# SCH_CJ4_Audiopanel.net
KiCad netlist of a schematic drawn in EasyEDA
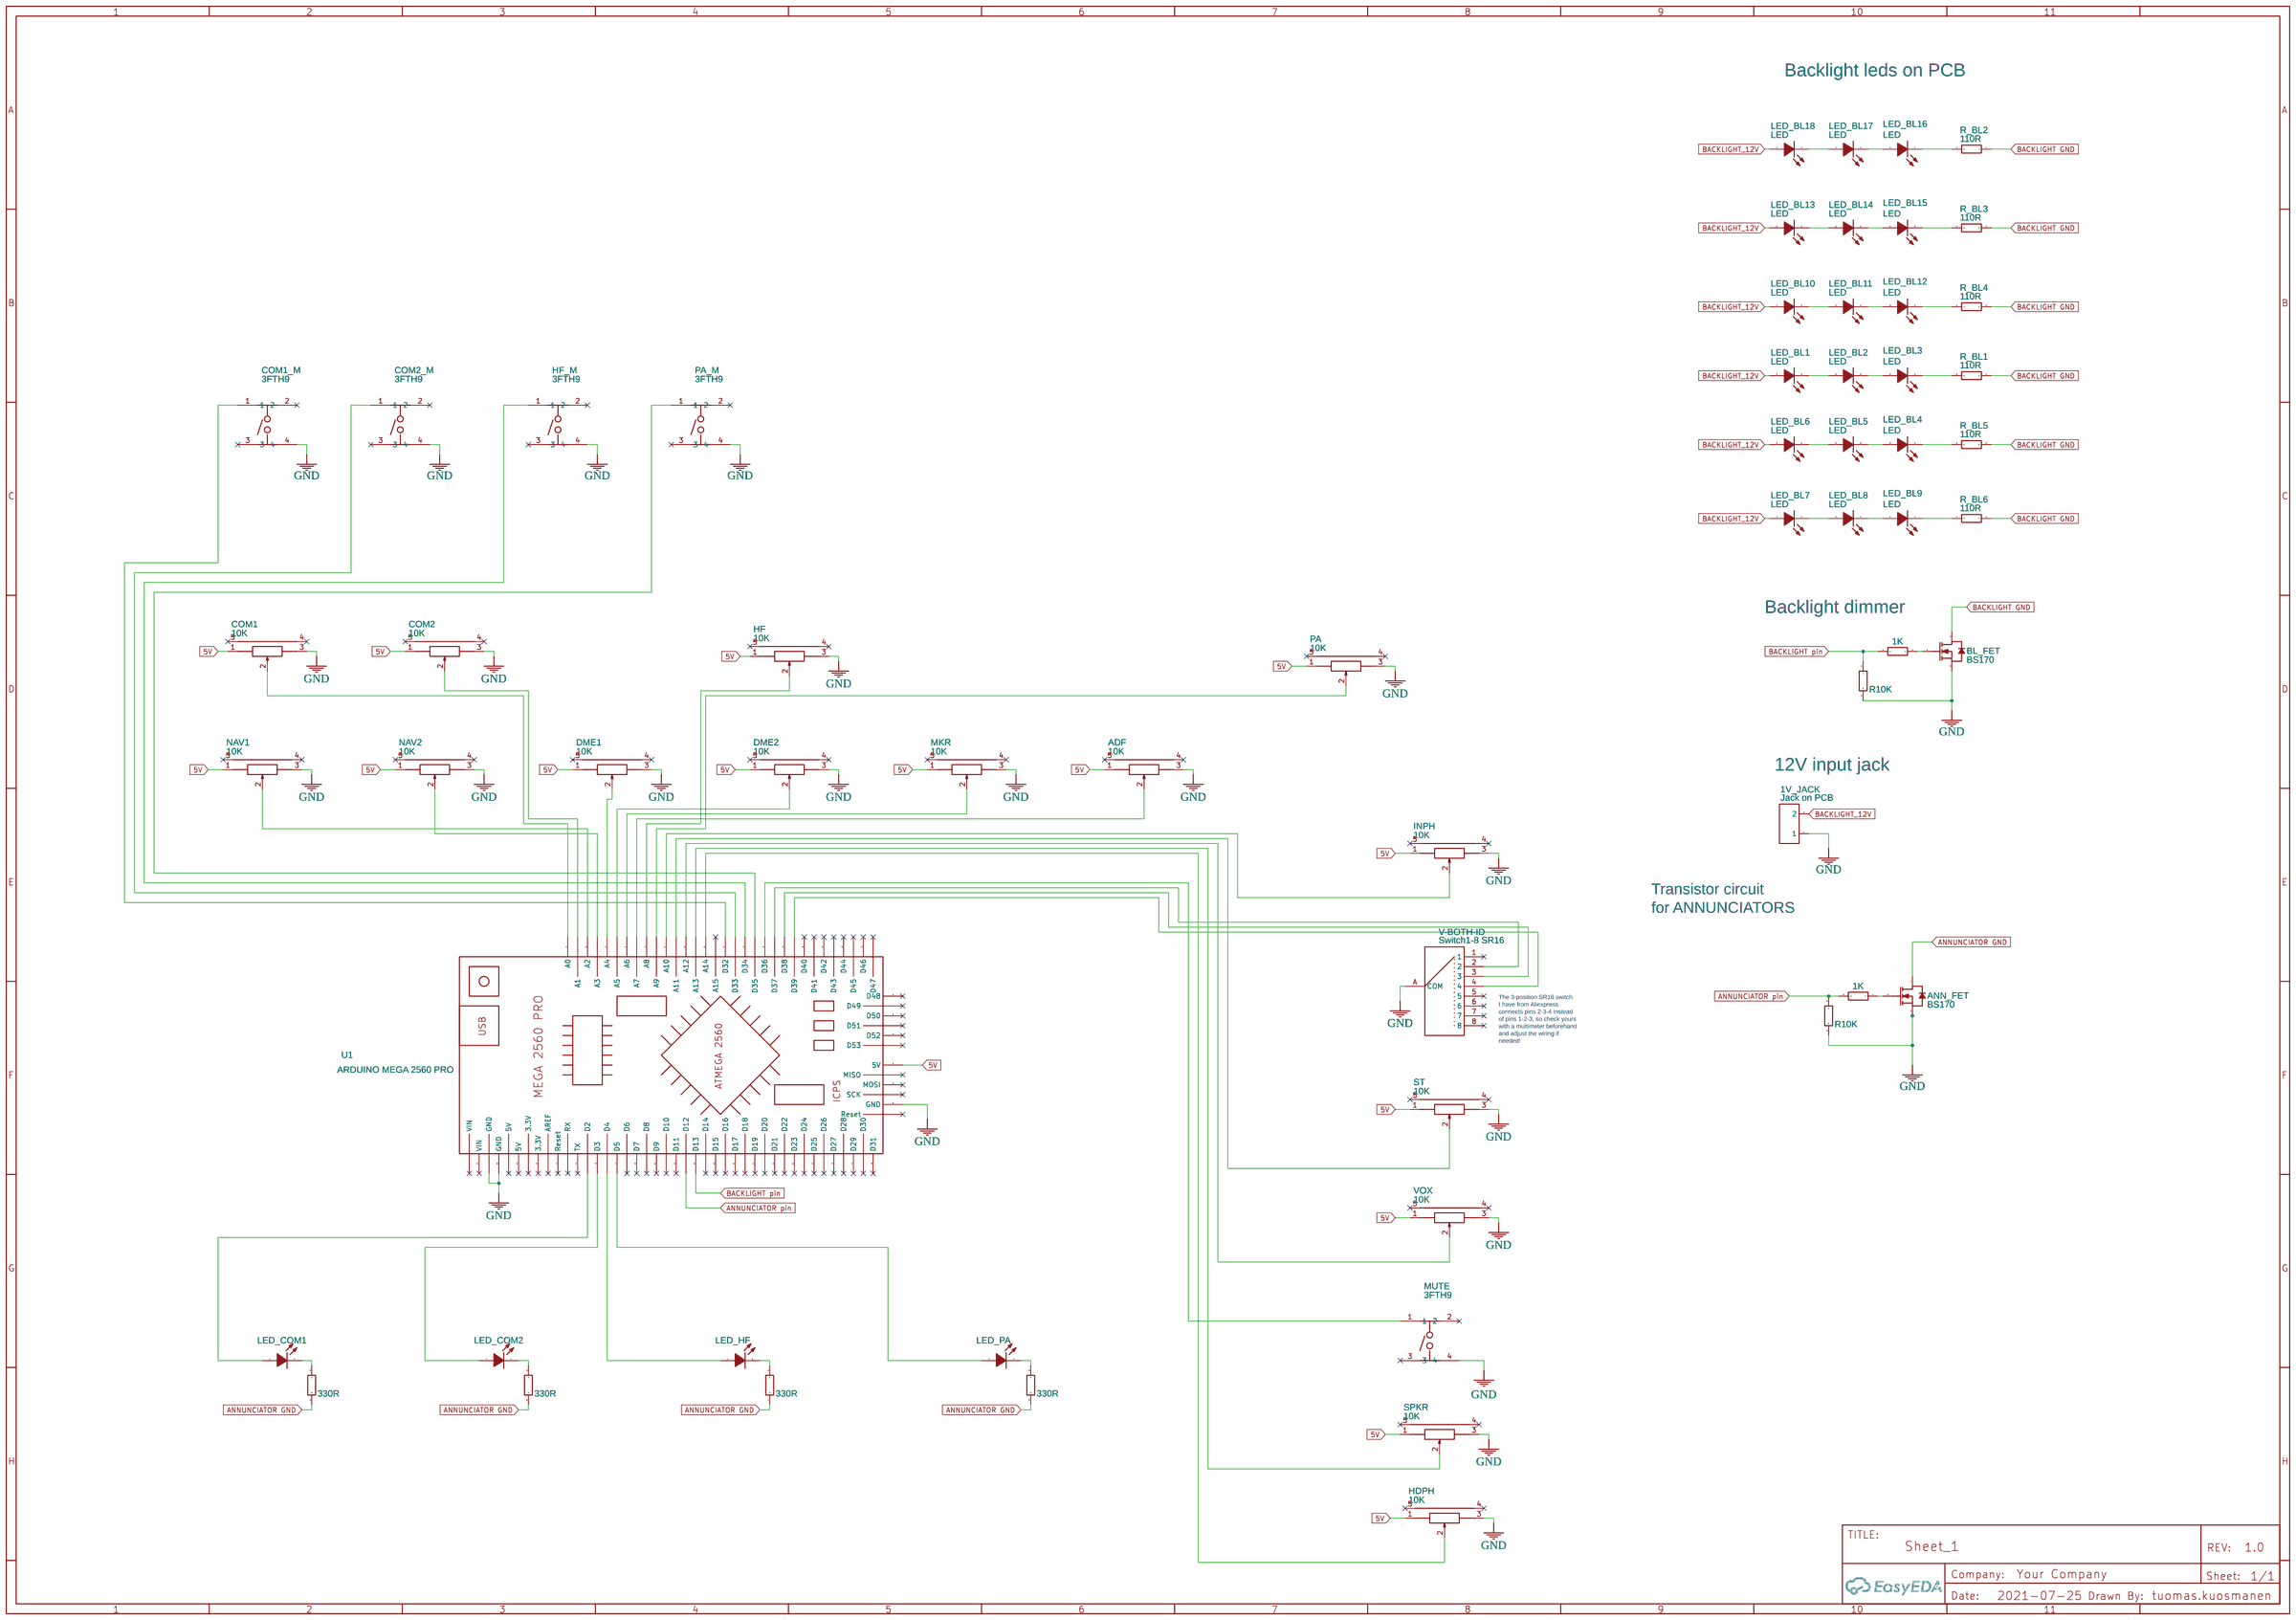
[diagram p0: schematic sheet]

(export (version "E")
  (design (tool "Eeschema 10.0.6"))
  (components
    (comp (ref "1MM_LED_THROUGH_HOLE")
      (value "LED_COM2")
      (fields
        (field (name "BOM_Manufacturer Part") "LEDOrange orange 3AO4UD")
        (field (name "BOM_Supplier Part") "C62095")
      )
      (libsource (lib "") (part "LEDOrange orange 3AO4UD_2"))
    )
    (comp (ref "1V_JACK") (value "Jack on PCB") (libsource (lib "") (part "J-Header-Male-2.54_1x2")))
    (comp (ref "1_SURFACE_MOUNT_RESISTOR")
      (value "330R")
      (fields
        (field (name "BOM_Manufacturer Part") "1206W4F330LT5E")
        (field (name "BOM_Supplier Part") "C25337")
      )
      (libsource (lib "") (part "1206W4F330LT5E"))
    )
    (comp (ref "2MM_LED_THROUGH_HOLE")
      (value "LED_HF")
      (fields
        (field (name "BOM_Manufacturer Part") "LEDOrange orange 3AO4UD")
        (field (name "BOM_Supplier Part") "C62095")
      )
      (libsource (lib "") (part "LEDOrange orange 3AO4UD_3"))
    )
    (comp (ref "2_SURFACE_MOUNT_RESISTOR")
      (value "330R")
      (fields
        (field (name "BOM_Manufacturer Part") "1206W4F330LT5E")
        (field (name "BOM_Supplier Part") "C25337")
      )
      (libsource (lib "") (part "1206W4F330LT5E_1"))
    )
    (comp (ref "3MM_LED_THROUGH_HOLE")
      (value "LED_PA")
      (fields
        (field (name "BOM_Manufacturer Part") "LEDOrange orange 3AO4UD")
        (field (name "BOM_Supplier Part") "C62095")
      )
      (libsource (lib "") (part "LEDOrange orange 3AO4UD_1"))
    )
    (comp (ref "3_SURFACE_MOUNT_RESISTOR")
      (value "330R")
      (fields
        (field (name "BOM_Manufacturer Part") "1206W4F330LT5E")
        (field (name "BOM_Supplier Part") "C25337")
      )
      (libsource (lib "") (part "1206W4F330LT5E_3"))
    )
    (comp (ref "4_SURFACE_MOUNT_RESISTOR")
      (value "330R")
      (fields
        (field (name "BOM_Manufacturer Part") "1206W4F330LT5E")
        (field (name "BOM_Supplier Part") "C25337")
      )
      (libsource (lib "") (part "1206W4F330LT5E_2"))
    )
    (comp (ref "5MM_LED_THROUGH_HOLE")
      (value "LED_COM1")
      (fields
        (field (name "BOM_Manufacturer Part") "LEDOrange orange 3AO4UD")
        (field (name "BOM_Supplier Part") "C62095")
      )
      (libsource (lib "") (part "LEDOrange orange 3AO4UD"))
    )
    (comp (ref "ADF")
      (value "10K")
      (fields
        (field (name "BOM_Manufacturer Part") "RK09K1130A70")
        (field (name "BOM_Supplier Part") "C351173")
      )
      (libsource (lib "") (part "RK09K1130A70_2"))
    )
    (comp (ref "ANN_FET")
      (value "BS170")
      (fields (field (name "BOM_Supplier Part") "C111691"))
      (libsource (lib "") (part "BS170"))
    )
    (comp (ref "BL_FET")
      (value "BS170")
      (fields (field (name "BOM_Supplier Part") "C111691"))
      (libsource (lib "") (part "BS170_1"))
    )
    (comp (ref "COM1")
      (value "10K")
      (fields
        (field (name "BOM_Manufacturer Part") "RK09K1130A70")
        (field (name "BOM_Supplier Part") "C351173")
      )
      (libsource (lib "") (part "RK09K1130A70_6"))
    )
    (comp (ref "COM1_M")
      (value "3FTH9")
      (fields (field (name "BOM_Supplier Part") "679-3730-5-ND"))
      (libsource (lib "") (part "3FTH9_2"))
    )
    (comp (ref "COM2")
      (value "10K")
      (fields
        (field (name "BOM_Manufacturer Part") "RK09K1130A70")
        (field (name "BOM_Supplier Part") "C351173")
      )
      (libsource (lib "") (part "RK09K1130A70_6"))
    )
    (comp (ref "COM2_M")
      (value "3FTH9")
      (fields (field (name "BOM_Supplier Part") "679-3730-5-ND"))
      (libsource (lib "") (part "3FTH9_3"))
    )
    (comp (ref "DME1")
      (value "10K")
      (fields
        (field (name "BOM_Manufacturer Part") "RK09K1130A70")
        (field (name "BOM_Supplier Part") "C351173")
      )
      (libsource (lib "") (part "RK09K1130A70_4"))
    )
    (comp (ref "DME2")
      (value "10K")
      (fields
        (field (name "BOM_Manufacturer Part") "RK09K1130A70")
        (field (name "BOM_Supplier Part") "C351173")
      )
      (libsource (lib "") (part "RK09K1130A70_4"))
    )
    (comp (ref "HDPH")
      (value "10K")
      (fields
        (field (name "BOM_Manufacturer Part") "RK09K1130A70")
        (field (name "BOM_Supplier Part") "C351173")
      )
      (libsource (lib "") (part "RK09K1130A70"))
    )
    (comp (ref "HF")
      (value "10K")
      (fields
        (field (name "BOM_Manufacturer Part") "RK09K1130A70")
        (field (name "BOM_Supplier Part") "C351173")
      )
      (libsource (lib "") (part "RK09K1130A70_1"))
    )
    (comp (ref "HF_M")
      (value "3FTH9")
      (fields (field (name "BOM_Supplier Part") "679-3730-5-ND"))
      (libsource (lib "") (part "3FTH9_1"))
    )
    (comp (ref "INPH")
      (value "10K")
      (fields
        (field (name "BOM_Manufacturer Part") "RK09K1130A70")
        (field (name "BOM_Supplier Part") "C351173")
      )
      (libsource (lib "") (part "RK09K1130A70_10"))
    )
    (comp (ref "LED_BL1")
      (value "LED")
      (fields
        (field (name "BOM_Manufacturer Part") "HQ17-2102UYOC")
        (field (name "BOM_Supplier Part") "C154481")
      )
      (libsource (lib "") (part "HQ17-2102UYOC"))
    )
    (comp (ref "LED_BL2")
      (value "LED")
      (fields
        (field (name "BOM_Manufacturer Part") "HQ17-2102UYOC")
        (field (name "BOM_Supplier Part") "C154481")
      )
      (libsource (lib "") (part "HQ17-2102UYOC"))
    )
    (comp (ref "LED_BL3")
      (value "LED")
      (fields
        (field (name "BOM_Manufacturer Part") "HQ17-2102UYOC")
        (field (name "BOM_Supplier Part") "C154481")
      )
      (libsource (lib "") (part "HQ17-2102UYOC"))
    )
    (comp (ref "LED_BL4")
      (value "LED")
      (fields
        (field (name "BOM_Manufacturer Part") "HQ17-2102UYOC")
        (field (name "BOM_Supplier Part") "C154481")
      )
      (libsource (lib "") (part "HQ17-2102UYOC"))
    )
    (comp (ref "LED_BL5")
      (value "LED")
      (fields
        (field (name "BOM_Manufacturer Part") "HQ17-2102UYOC")
        (field (name "BOM_Supplier Part") "C154481")
      )
      (libsource (lib "") (part "HQ17-2102UYOC"))
    )
    (comp (ref "LED_BL6")
      (value "LED")
      (fields
        (field (name "BOM_Manufacturer Part") "HQ17-2102UYOC")
        (field (name "BOM_Supplier Part") "C154481")
      )
      (libsource (lib "") (part "HQ17-2102UYOC"))
    )
    (comp (ref "LED_BL7")
      (value "LED")
      (fields
        (field (name "BOM_Manufacturer Part") "HQ17-2102UYOC")
        (field (name "BOM_Supplier Part") "C154481")
      )
      (libsource (lib "") (part "HQ17-2102UYOC"))
    )
    (comp (ref "LED_BL8")
      (value "LED")
      (fields
        (field (name "BOM_Manufacturer Part") "HQ17-2102UYOC")
        (field (name "BOM_Supplier Part") "C154481")
      )
      (libsource (lib "") (part "HQ17-2102UYOC"))
    )
    (comp (ref "LED_BL9")
      (value "LED")
      (fields
        (field (name "BOM_Manufacturer Part") "HQ17-2102UYOC")
        (field (name "BOM_Supplier Part") "C154481")
      )
      (libsource (lib "") (part "HQ17-2102UYOC"))
    )
    (comp (ref "LED_BL10")
      (value "LED")
      (fields
        (field (name "BOM_Manufacturer Part") "HQ17-2102UYOC")
        (field (name "BOM_Supplier Part") "C154481")
      )
      (libsource (lib "") (part "HQ17-2102UYOC"))
    )
    (comp (ref "LED_BL11")
      (value "LED")
      (fields
        (field (name "BOM_Manufacturer Part") "HQ17-2102UYOC")
        (field (name "BOM_Supplier Part") "C154481")
      )
      (libsource (lib "") (part "HQ17-2102UYOC"))
    )
    (comp (ref "LED_BL12")
      (value "LED")
      (fields
        (field (name "BOM_Manufacturer Part") "HQ17-2102UYOC")
        (field (name "BOM_Supplier Part") "C154481")
      )
      (libsource (lib "") (part "HQ17-2102UYOC"))
    )
    (comp (ref "LED_BL13")
      (value "LED")
      (fields
        (field (name "BOM_Manufacturer Part") "HQ17-2102UYOC")
        (field (name "BOM_Supplier Part") "C154481")
      )
      (libsource (lib "") (part "HQ17-2102UYOC"))
    )
    (comp (ref "LED_BL14")
      (value "LED")
      (fields
        (field (name "BOM_Manufacturer Part") "HQ17-2102UYOC")
        (field (name "BOM_Supplier Part") "C154481")
      )
      (libsource (lib "") (part "HQ17-2102UYOC"))
    )
    (comp (ref "LED_BL15")
      (value "LED")
      (fields
        (field (name "BOM_Manufacturer Part") "HQ17-2102UYOC")
        (field (name "BOM_Supplier Part") "C154481")
      )
      (libsource (lib "") (part "HQ17-2102UYOC"))
    )
    (comp (ref "LED_BL16")
      (value "LED")
      (fields
        (field (name "BOM_Manufacturer Part") "HQ17-2102UYOC")
        (field (name "BOM_Supplier Part") "C154481")
      )
      (libsource (lib "") (part "HQ17-2102UYOC"))
    )
    (comp (ref "LED_BL17")
      (value "LED")
      (fields
        (field (name "BOM_Manufacturer Part") "HQ17-2102UYOC")
        (field (name "BOM_Supplier Part") "C154481")
      )
      (libsource (lib "") (part "HQ17-2102UYOC"))
    )
    (comp (ref "LED_BL18")
      (value "LED")
      (fields
        (field (name "BOM_Manufacturer Part") "HQ17-2102UYOC")
        (field (name "BOM_Supplier Part") "C154481")
      )
      (libsource (lib "") (part "HQ17-2102UYOC"))
    )
    (comp (ref "MKR")
      (value "10K")
      (fields
        (field (name "BOM_Manufacturer Part") "RK09K1130A70")
        (field (name "BOM_Supplier Part") "C351173")
      )
      (libsource (lib "") (part "RK09K1130A70_3"))
    )
    (comp (ref "MUTE")
      (value "3FTH9")
      (fields (field (name "BOM_Supplier Part") "679-3730-5-ND"))
      (libsource (lib "") (part "3FTH9_4"))
    )
    (comp (ref "NAV1")
      (value "10K")
      (fields
        (field (name "BOM_Manufacturer Part") "RK09K1130A70")
        (field (name "BOM_Supplier Part") "C351173")
      )
      (libsource (lib "") (part "RK09K1130A70_8"))
    )
    (comp (ref "NAV2")
      (value "10K")
      (fields
        (field (name "BOM_Manufacturer Part") "RK09K1130A70")
        (field (name "BOM_Supplier Part") "C351173")
      )
      (libsource (lib "") (part "RK09K1130A70_8"))
    )
    (comp (ref "PA")
      (value "10K")
      (fields
        (field (name "BOM_Manufacturer Part") "RK09K1130A70")
        (field (name "BOM_Supplier Part") "C351173")
      )
      (libsource (lib "") (part "RK09K1130A70_5"))
    )
    (comp (ref "PA_M")
      (value "3FTH9")
      (fields (field (name "BOM_Supplier Part") "679-3730-5-ND"))
      (libsource (lib "") (part "3FTH9"))
    )
    (comp (ref "R_ANN1")
      (value "1K")
      (fields
        (field (name "BOM_Manufacturer Part") "1206W4J0331T5E")
        (field (name "BOM_Supplier Part") "C25374")
      )
      (libsource (lib "") (part "1206W4J0331T5E_1"))
    )
    (comp (ref "R_ANN2")
      (value "R10K")
      (fields
        (field (name "BOM_Manufacturer Part") "1206W4J0331T5E")
        (field (name "BOM_Supplier Part") "C25374")
      )
      (libsource (lib "") (part "1206W4J0331T5E_2"))
    )
    (comp (ref "R_ANN3")
      (value "R10K")
      (fields
        (field (name "BOM_Manufacturer Part") "1206W4J0331T5E")
        (field (name "BOM_Supplier Part") "C25374")
      )
      (libsource (lib "") (part "1206W4J0331T5E_2"))
    )
    (comp (ref "R_ANN4")
      (value "1K")
      (fields
        (field (name "BOM_Manufacturer Part") "1206W4J0331T5E")
        (field (name "BOM_Supplier Part") "C25374")
      )
      (libsource (lib "") (part "1206W4J0331T5E_1"))
    )
    (comp (ref "R_BL1")
      (value "110R")
      (fields
        (field (name "BOM_Manufacturer Part") "1206W4J0331T5E")
        (field (name "BOM_Supplier Part") "C25374")
      )
      (libsource (lib "") (part "1206W4J0331T5E"))
    )
    (comp (ref "R_BL2")
      (value "110R")
      (fields
        (field (name "BOM_Manufacturer Part") "1206W4J0331T5E")
        (field (name "BOM_Supplier Part") "C25374")
      )
      (libsource (lib "") (part "1206W4J0331T5E"))
    )
    (comp (ref "R_BL3")
      (value "110R")
      (fields
        (field (name "BOM_Manufacturer Part") "1206W4J0331T5E")
        (field (name "BOM_Supplier Part") "C25374")
      )
      (libsource (lib "") (part "1206W4J0331T5E"))
    )
    (comp (ref "R_BL4")
      (value "110R")
      (fields
        (field (name "BOM_Manufacturer Part") "1206W4J0331T5E")
        (field (name "BOM_Supplier Part") "C25374")
      )
      (libsource (lib "") (part "1206W4J0331T5E"))
    )
    (comp (ref "R_BL5")
      (value "110R")
      (fields
        (field (name "BOM_Manufacturer Part") "1206W4J0331T5E")
        (field (name "BOM_Supplier Part") "C25374")
      )
      (libsource (lib "") (part "1206W4J0331T5E"))
    )
    (comp (ref "R_BL6")
      (value "110R")
      (fields
        (field (name "BOM_Manufacturer Part") "1206W4J0331T5E")
        (field (name "BOM_Supplier Part") "C25374")
      )
      (libsource (lib "") (part "1206W4J0331T5E"))
    )
    (comp (ref "SPKR")
      (value "10K")
      (fields
        (field (name "BOM_Manufacturer Part") "RK09K1130A70")
        (field (name "BOM_Supplier Part") "C351173")
      )
      (libsource (lib "") (part "RK09K1130A70_11"))
    )
    (comp (ref "ST")
      (value "10K")
      (fields
        (field (name "BOM_Manufacturer Part") "RK09K1130A70")
        (field (name "BOM_Supplier Part") "C351173")
      )
      (libsource (lib "") (part "RK09K1130A70_9"))
    )
    (comp (ref "U1")
      (value "ARDUINO MEGA 2560 PRO")
      (fields (field (name "BOM_Manufacturer Part") "Arduino Mega 2560 Pro Mini"))
      (libsource (lib "") (part "ARDUINO MEGA 2560 PRO"))
    )
    (comp (ref "V-BOTH-ID")
      (value "Switch1-8 SR16")
      (fields (field (name "BOM_Supplier Part") "SR16_1/8"))
      (libsource (lib "") (part "Switch1-8 SR16"))
    )
    (comp (ref "VOX")
      (value "10K")
      (fields
        (field (name "BOM_Manufacturer Part") "RK09K1130A70")
        (field (name "BOM_Supplier Part") "C351173")
      )
      (libsource (lib "") (part "RK09K1130A70_7"))
    )
  )
  (nets
    (net (code "1") (name "5V") (class "Default")
      (node (ref "ADF") (pin "1") (pinfunction "1_1") (pintype "unspecified"))
      (node (ref "COM1") (pin "1") (pinfunction "1_1") (pintype "unspecified"))
      (node (ref "COM2") (pin "1") (pinfunction "1_1") (pintype "unspecified"))
      (node (ref "DME1") (pin "1") (pinfunction "1_1") (pintype "unspecified"))
      (node (ref "DME2") (pin "1") (pinfunction "1_1") (pintype "unspecified"))
      (node (ref "HDPH") (pin "1") (pinfunction "1_1") (pintype "unspecified"))
      (node (ref "HF") (pin "1") (pinfunction "1_1") (pintype "unspecified"))
      (node (ref "INPH") (pin "1") (pinfunction "1_1") (pintype "unspecified"))
      (node (ref "MKR") (pin "1") (pinfunction "1_1") (pintype "unspecified"))
      (node (ref "NAV1") (pin "1") (pinfunction "1_1") (pintype "unspecified"))
      (node (ref "NAV2") (pin "1") (pinfunction "1_1") (pintype "unspecified"))
      (node (ref "PA") (pin "1") (pinfunction "1_1") (pintype "unspecified"))
      (node (ref "SPKR") (pin "1") (pinfunction "1_1") (pintype "unspecified"))
      (node (ref "ST") (pin "1") (pinfunction "1_1") (pintype "unspecified"))
      (node (ref "U1") (pin "39") (pinfunction "5V_39") (pintype "unspecified"))
      (node (ref "VOX") (pin "1") (pinfunction "1_1") (pintype "unspecified"))
    )
    (net (code "2") (name "ANNUNCIATOR GND") (class "Default")
      (node (ref "1_SURFACE_MOUNT_RESISTOR") (pin "1") (pinfunction "1_1") (pintype "input"))
      (node (ref "2_SURFACE_MOUNT_RESISTOR") (pin "1") (pinfunction "1_1") (pintype "input"))
      (node (ref "3_SURFACE_MOUNT_RESISTOR") (pin "1") (pinfunction "1_1") (pintype "input"))
      (node (ref "4_SURFACE_MOUNT_RESISTOR") (pin "1") (pinfunction "1_1") (pintype "input"))
      (node (ref "ANN_FET") (pin "1") (pinfunction "D_1") (pintype "unspecified"))
    )
    (net (code "3") (name "ANNUNCIATOR pin") (class "Default")
      (node (ref "R_ANN1") (pin "2") (pinfunction "2_2") (pintype "input"))
      (node (ref "R_ANN2") (pin "1") (pinfunction "1_1") (pintype "input"))
      (node (ref "U1") (pin "64") (pinfunction "D12_64") (pintype "unspecified"))
    )
    (net (code "4") (name "BACKLIGHT GND") (class "Default")
      (node (ref "BL_FET") (pin "1") (pinfunction "D_1") (pintype "unspecified"))
      (node (ref "R_BL1") (pin "1") (pinfunction "1_1") (pintype "input"))
      (node (ref "R_BL2") (pin "1") (pinfunction "1_1") (pintype "input"))
      (node (ref "R_BL3") (pin "1") (pinfunction "1_1") (pintype "input"))
      (node (ref "R_BL4") (pin "1") (pinfunction "1_1") (pintype "input"))
      (node (ref "R_BL5") (pin "1") (pinfunction "1_1") (pintype "input"))
      (node (ref "R_BL6") (pin "1") (pinfunction "1_1") (pintype "input"))
    )
    (net (code "5") (name "BACKLIGHT pin") (class "Default")
      (node (ref "R_ANN3") (pin "1") (pinfunction "1_1") (pintype "input"))
      (node (ref "R_ANN4") (pin "2") (pinfunction "2_2") (pintype "input"))
      (node (ref "U1") (pin "63") (pinfunction "D13_63") (pintype "unspecified"))
    )
    (net (code "6") (name "BACKLIGHT_12V") (class "Default")
      (node (ref "1V_JACK") (pin "2") (pinfunction "2_2") (pintype "unspecified"))
      (node (ref "LED_BL1") (pin "2") (pinfunction "A_2") (pintype "unspecified"))
      (node (ref "LED_BL10") (pin "2") (pinfunction "A_2") (pintype "unspecified"))
      (node (ref "LED_BL13") (pin "2") (pinfunction "A_2") (pintype "unspecified"))
      (node (ref "LED_BL18") (pin "2") (pinfunction "A_2") (pintype "unspecified"))
      (node (ref "LED_BL6") (pin "2") (pinfunction "A_2") (pintype "unspecified"))
      (node (ref "LED_BL7") (pin "2") (pinfunction "A_2") (pintype "unspecified"))
    )
    (net (code "7") (name "GND") (class "Default")
      (node (ref "1V_JACK") (pin "1") (pinfunction "1_1") (pintype "unspecified"))
      (node (ref "ADF") (pin "3") (pinfunction "3_3") (pintype "unspecified"))
      (node (ref "ANN_FET") (pin "3") (pinfunction "S_3") (pintype "unspecified"))
      (node (ref "BL_FET") (pin "3") (pinfunction "S_3") (pintype "unspecified"))
      (node (ref "COM1") (pin "3") (pinfunction "3_3") (pintype "unspecified"))
      (node (ref "COM1_M") (pin "4") (pinfunction "4_4") (pintype "unspecified"))
      (node (ref "COM2") (pin "3") (pinfunction "3_3") (pintype "unspecified"))
      (node (ref "COM2_M") (pin "4") (pinfunction "4_4") (pintype "unspecified"))
      (node (ref "DME1") (pin "3") (pinfunction "3_3") (pintype "unspecified"))
      (node (ref "DME2") (pin "3") (pinfunction "3_3") (pintype "unspecified"))
      (node (ref "HDPH") (pin "3") (pinfunction "3_3") (pintype "unspecified"))
      (node (ref "HF") (pin "3") (pinfunction "3_3") (pintype "unspecified"))
      (node (ref "HF_M") (pin "4") (pinfunction "4_4") (pintype "unspecified"))
      (node (ref "INPH") (pin "3") (pinfunction "3_3") (pintype "unspecified"))
      (node (ref "MKR") (pin "3") (pinfunction "3_3") (pintype "unspecified"))
      (node (ref "MUTE") (pin "4") (pinfunction "4_4") (pintype "unspecified"))
      (node (ref "NAV1") (pin "3") (pinfunction "3_3") (pintype "unspecified"))
      (node (ref "NAV2") (pin "3") (pinfunction "3_3") (pintype "unspecified"))
      (node (ref "PA") (pin "3") (pinfunction "3_3") (pintype "unspecified"))
      (node (ref "PA_M") (pin "4") (pinfunction "4_4") (pintype "unspecified"))
      (node (ref "R_ANN2") (pin "2") (pinfunction "2_2") (pintype "input"))
      (node (ref "R_ANN3") (pin "2") (pinfunction "2_2") (pintype "input"))
      (node (ref "SPKR") (pin "3") (pinfunction "3_3") (pintype "unspecified"))
      (node (ref "ST") (pin "3") (pinfunction "3_3") (pintype "unspecified"))
      (node (ref "U1") (pin "43") (pinfunction "GND_43") (pintype "unspecified"))
      (node (ref "U1") (pin "83") (pinfunction "GND_83") (pintype "unspecified"))
      (node (ref "U1") (pin "84") (pinfunction "GND_84") (pintype "unspecified"))
      (node (ref "V-BOTH-ID") (pin "A") (pinfunction "COM_A") (pintype "unspecified"))
      (node (ref "VOX") (pin "3") (pinfunction "3_3") (pintype "unspecified"))
    )
    (net (code "8") (name "Net-(1MM_LED_THROUGH_HOLE-A)") (class "Default")
      (node (ref "1MM_LED_THROUGH_HOLE") (pin "1") (pinfunction "A_1") (pintype "unspecified"))
      (node (ref "U1") (pin "73") (pinfunction "D3_73") (pintype "unspecified"))
    )
    (net (code "9") (name "Net-(1MM_LED_THROUGH_HOLE-K)") (class "Default")
      (node (ref "1MM_LED_THROUGH_HOLE") (pin "2") (pinfunction "K_2") (pintype "unspecified"))
      (node (ref "1_SURFACE_MOUNT_RESISTOR") (pin "2") (pinfunction "2_2") (pintype "input"))
    )
    (net (code "10") (name "Net-(2MM_LED_THROUGH_HOLE-A)") (class "Default")
      (node (ref "2MM_LED_THROUGH_HOLE") (pin "1") (pinfunction "A_1") (pintype "unspecified"))
      (node (ref "U1") (pin "72") (pinfunction "D4_72") (pintype "unspecified"))
    )
    (net (code "11") (name "Net-(2MM_LED_THROUGH_HOLE-K)") (class "Default")
      (node (ref "2MM_LED_THROUGH_HOLE") (pin "2") (pinfunction "K_2") (pintype "unspecified"))
      (node (ref "3_SURFACE_MOUNT_RESISTOR") (pin "2") (pinfunction "2_2") (pintype "input"))
    )
    (net (code "12") (name "Net-(3MM_LED_THROUGH_HOLE-A)") (class "Default")
      (node (ref "3MM_LED_THROUGH_HOLE") (pin "1") (pinfunction "A_1") (pintype "unspecified"))
      (node (ref "U1") (pin "71") (pinfunction "D5_71") (pintype "unspecified"))
    )
    (net (code "13") (name "Net-(3MM_LED_THROUGH_HOLE-K)") (class "Default")
      (node (ref "3MM_LED_THROUGH_HOLE") (pin "2") (pinfunction "K_2") (pintype "unspecified"))
      (node (ref "4_SURFACE_MOUNT_RESISTOR") (pin "2") (pinfunction "2_2") (pintype "input"))
    )
    (net (code "14") (name "Net-(5MM_LED_THROUGH_HOLE-A)") (class "Default")
      (node (ref "5MM_LED_THROUGH_HOLE") (pin "1") (pinfunction "A_1") (pintype "unspecified"))
      (node (ref "U1") (pin "74") (pinfunction "D2_74") (pintype "unspecified"))
    )
    (net (code "15") (name "Net-(5MM_LED_THROUGH_HOLE-K)") (class "Default")
      (node (ref "2_SURFACE_MOUNT_RESISTOR") (pin "2") (pinfunction "2_2") (pintype "input"))
      (node (ref "5MM_LED_THROUGH_HOLE") (pin "2") (pinfunction "K_2") (pintype "unspecified"))
    )
    (net (code "16") (name "Net-(ANN_FET-G)") (class "Default")
      (node (ref "ANN_FET") (pin "2") (pinfunction "G_2") (pintype "unspecified"))
      (node (ref "R_ANN1") (pin "1") (pinfunction "1_1") (pintype "input"))
    )
    (net (code "17") (name "Net-(BL_FET-G)") (class "Default")
      (node (ref "BL_FET") (pin "2") (pinfunction "G_2") (pintype "unspecified"))
      (node (ref "R_ANN4") (pin "1") (pinfunction "1_1") (pintype "input"))
    )
    (net (code "18") (name "Net-(LED_BL1-K)") (class "Default")
      (node (ref "LED_BL1") (pin "1") (pinfunction "K_1") (pintype "unspecified"))
      (node (ref "LED_BL2") (pin "2") (pinfunction "A_2") (pintype "unspecified"))
    )
    (net (code "19") (name "Net-(LED_BL2-K)") (class "Default")
      (node (ref "LED_BL2") (pin "1") (pinfunction "K_1") (pintype "unspecified"))
      (node (ref "LED_BL3") (pin "2") (pinfunction "A_2") (pintype "unspecified"))
    )
    (net (code "20") (name "Net-(LED_BL3-K)") (class "Default")
      (node (ref "LED_BL3") (pin "1") (pinfunction "K_1") (pintype "unspecified"))
      (node (ref "R_BL1") (pin "2") (pinfunction "2_2") (pintype "input"))
    )
    (net (code "21") (name "Net-(LED_BL4-A)") (class "Default")
      (node (ref "LED_BL4") (pin "2") (pinfunction "A_2") (pintype "unspecified"))
      (node (ref "LED_BL5") (pin "1") (pinfunction "K_1") (pintype "unspecified"))
    )
    (net (code "22") (name "Net-(LED_BL4-K)") (class "Default")
      (node (ref "LED_BL4") (pin "1") (pinfunction "K_1") (pintype "unspecified"))
      (node (ref "R_BL5") (pin "2") (pinfunction "2_2") (pintype "input"))
    )
    (net (code "23") (name "Net-(LED_BL5-A)") (class "Default")
      (node (ref "LED_BL5") (pin "2") (pinfunction "A_2") (pintype "unspecified"))
      (node (ref "LED_BL6") (pin "1") (pinfunction "K_1") (pintype "unspecified"))
    )
    (net (code "24") (name "Net-(LED_BL7-K)") (class "Default")
      (node (ref "LED_BL7") (pin "1") (pinfunction "K_1") (pintype "unspecified"))
      (node (ref "LED_BL8") (pin "2") (pinfunction "A_2") (pintype "unspecified"))
    )
    (net (code "25") (name "Net-(LED_BL8-K)") (class "Default")
      (node (ref "LED_BL8") (pin "1") (pinfunction "K_1") (pintype "unspecified"))
      (node (ref "LED_BL9") (pin "2") (pinfunction "A_2") (pintype "unspecified"))
    )
    (net (code "26") (name "Net-(LED_BL9-K)") (class "Default")
      (node (ref "LED_BL9") (pin "1") (pinfunction "K_1") (pintype "unspecified"))
      (node (ref "R_BL6") (pin "2") (pinfunction "2_2") (pintype "input"))
    )
    (net (code "27") (name "Net-(LED_BL10-K)") (class "Default")
      (node (ref "LED_BL10") (pin "1") (pinfunction "K_1") (pintype "unspecified"))
      (node (ref "LED_BL11") (pin "2") (pinfunction "A_2") (pintype "unspecified"))
    )
    (net (code "28") (name "Net-(LED_BL11-K)") (class "Default")
      (node (ref "LED_BL11") (pin "1") (pinfunction "K_1") (pintype "unspecified"))
      (node (ref "LED_BL12") (pin "2") (pinfunction "A_2") (pintype "unspecified"))
    )
    (net (code "29") (name "Net-(LED_BL12-K)") (class "Default")
      (node (ref "LED_BL12") (pin "1") (pinfunction "K_1") (pintype "unspecified"))
      (node (ref "R_BL4") (pin "2") (pinfunction "2_2") (pintype "input"))
    )
    (net (code "30") (name "Net-(LED_BL13-K)") (class "Default")
      (node (ref "LED_BL13") (pin "1") (pinfunction "K_1") (pintype "unspecified"))
      (node (ref "LED_BL14") (pin "2") (pinfunction "A_2") (pintype "unspecified"))
    )
    (net (code "31") (name "Net-(LED_BL14-K)") (class "Default")
      (node (ref "LED_BL14") (pin "1") (pinfunction "K_1") (pintype "unspecified"))
      (node (ref "LED_BL15") (pin "2") (pinfunction "A_2") (pintype "unspecified"))
    )
    (net (code "32") (name "Net-(LED_BL15-K)") (class "Default")
      (node (ref "LED_BL15") (pin "1") (pinfunction "K_1") (pintype "unspecified"))
      (node (ref "R_BL3") (pin "2") (pinfunction "2_2") (pintype "input"))
    )
    (net (code "33") (name "Net-(LED_BL16-A)") (class "Default")
      (node (ref "LED_BL16") (pin "2") (pinfunction "A_2") (pintype "unspecified"))
      (node (ref "LED_BL17") (pin "1") (pinfunction "K_1") (pintype "unspecified"))
    )
    (net (code "34") (name "Net-(LED_BL16-K)") (class "Default")
      (node (ref "LED_BL16") (pin "1") (pinfunction "K_1") (pintype "unspecified"))
      (node (ref "R_BL2") (pin "2") (pinfunction "2_2") (pintype "input"))
    )
    (net (code "35") (name "Net-(LED_BL17-A)") (class "Default")
      (node (ref "LED_BL17") (pin "2") (pinfunction "A_2") (pintype "unspecified"))
      (node (ref "LED_BL18") (pin "1") (pinfunction "K_1") (pintype "unspecified"))
    )
    (net (code "36") (name "Net-(U1-A0)") (class "Default")
      (node (ref "COM1") (pin "2") (pinfunction "2_2") (pintype "unspecified"))
      (node (ref "U1") (pin "1") (pinfunction "A0_1") (pintype "unspecified"))
    )
    (net (code "37") (name "Net-(U1-A1)") (class "Default")
      (node (ref "COM2") (pin "2") (pinfunction "2_2") (pintype "unspecified"))
      (node (ref "U1") (pin "2") (pinfunction "A1_2") (pintype "unspecified"))
    )
    (net (code "38") (name "Net-(U1-A2)") (class "Default")
      (node (ref "NAV1") (pin "2") (pinfunction "2_2") (pintype "unspecified"))
      (node (ref "U1") (pin "3") (pinfunction "A2_3") (pintype "unspecified"))
    )
    (net (code "39") (name "Net-(U1-A3)") (class "Default")
      (node (ref "NAV2") (pin "2") (pinfunction "2_2") (pintype "unspecified"))
      (node (ref "U1") (pin "4") (pinfunction "A3_4") (pintype "unspecified"))
    )
    (net (code "40") (name "Net-(U1-A4)") (class "Default")
      (node (ref "DME1") (pin "2") (pinfunction "2_2") (pintype "unspecified"))
      (node (ref "U1") (pin "5") (pinfunction "A4_5") (pintype "unspecified"))
    )
    (net (code "41") (name "Net-(U1-A5)") (class "Default")
      (node (ref "DME2") (pin "2") (pinfunction "2_2") (pintype "unspecified"))
      (node (ref "U1") (pin "6") (pinfunction "A5_6") (pintype "unspecified"))
    )
    (net (code "42") (name "Net-(U1-A6)") (class "Default")
      (node (ref "MKR") (pin "2") (pinfunction "2_2") (pintype "unspecified"))
      (node (ref "U1") (pin "7") (pinfunction "A6_7") (pintype "unspecified"))
    )
    (net (code "43") (name "Net-(U1-A7)") (class "Default")
      (node (ref "ADF") (pin "2") (pinfunction "2_2") (pintype "unspecified"))
      (node (ref "U1") (pin "8") (pinfunction "A7_8") (pintype "unspecified"))
    )
    (net (code "44") (name "Net-(U1-A8)") (class "Default")
      (node (ref "HF") (pin "2") (pinfunction "2_2") (pintype "unspecified"))
      (node (ref "U1") (pin "9") (pinfunction "A8_9") (pintype "unspecified"))
    )
    (net (code "45") (name "Net-(U1-A9)") (class "Default")
      (node (ref "PA") (pin "2") (pinfunction "2_2") (pintype "unspecified"))
      (node (ref "U1") (pin "10") (pinfunction "A9_10") (pintype "unspecified"))
    )
    (net (code "46") (name "Net-(U1-A10)") (class "Default")
      (node (ref "INPH") (pin "2") (pinfunction "2_2") (pintype "unspecified"))
      (node (ref "U1") (pin "11") (pinfunction "A10_11") (pintype "unspecified"))
    )
    (net (code "47") (name "Net-(U1-A11)") (class "Default")
      (node (ref "ST") (pin "2") (pinfunction "2_2") (pintype "unspecified"))
      (node (ref "U1") (pin "12") (pinfunction "A11_12") (pintype "unspecified"))
    )
    (net (code "48") (name "Net-(U1-A12)") (class "Default")
      (node (ref "U1") (pin "13") (pinfunction "A12_13") (pintype "unspecified"))
      (node (ref "VOX") (pin "2") (pinfunction "2_2") (pintype "unspecified"))
    )
    (net (code "49") (name "Net-(U1-A13)") (class "Default")
      (node (ref "SPKR") (pin "2") (pinfunction "2_2") (pintype "unspecified"))
      (node (ref "U1") (pin "14") (pinfunction "A13_14") (pintype "unspecified"))
    )
    (net (code "50") (name "Net-(U1-A14)") (class "Default")
      (node (ref "HDPH") (pin "2") (pinfunction "2_2") (pintype "unspecified"))
      (node (ref "U1") (pin "15") (pinfunction "A14_15") (pintype "unspecified"))
    )
    (net (code "51") (name "Net-(U1-D32)") (class "Default")
      (node (ref "COM1_M") (pin "1") (pinfunction "1_1") (pintype "unspecified"))
      (node (ref "U1") (pin "17") (pinfunction "D32_17") (pintype "unspecified"))
    )
    (net (code "52") (name "Net-(U1-D33)") (class "Default")
      (node (ref "COM2_M") (pin "1") (pinfunction "1_1") (pintype "unspecified"))
      (node (ref "U1") (pin "18") (pinfunction "D33_18") (pintype "unspecified"))
    )
    (net (code "53") (name "Net-(U1-D34)") (class "Default")
      (node (ref "HF_M") (pin "1") (pinfunction "1_1") (pintype "unspecified"))
      (node (ref "U1") (pin "19") (pinfunction "D34_19") (pintype "unspecified"))
    )
    (net (code "54") (name "Net-(U1-D35)") (class "Default")
      (node (ref "PA_M") (pin "1") (pinfunction "1_1") (pintype "unspecified"))
      (node (ref "U1") (pin "20") (pinfunction "D35_20") (pintype "unspecified"))
    )
    (net (code "55") (name "Net-(U1-D36)") (class "Default")
      (node (ref "MUTE") (pin "1") (pinfunction "1_1") (pintype "unspecified"))
      (node (ref "U1") (pin "21") (pinfunction "D36_21") (pintype "unspecified"))
    )
    (net (code "56") (name "Net-(U1-D37)") (class "Default")
      (node (ref "U1") (pin "22") (pinfunction "D37_22") (pintype "unspecified"))
      (node (ref "V-BOTH-ID") (pin "2") (pinfunction "2_2") (pintype "unspecified"))
    )
    (net (code "57") (name "Net-(U1-D38)") (class "Default")
      (node (ref "U1") (pin "23") (pinfunction "D38_23") (pintype "unspecified"))
      (node (ref "V-BOTH-ID") (pin "3") (pinfunction "3_3") (pintype "unspecified"))
    )
    (net (code "58") (name "Net-(U1-D39)") (class "Default")
      (node (ref "U1") (pin "24") (pinfunction "D39_24") (pintype "unspecified"))
      (node (ref "V-BOTH-ID") (pin "4") (pinfunction "4_4") (pintype "unspecified"))
    )
    (net (code "59") (name "unconnected-(ADF-EH-Pad4)") (class "Default")
      (node (ref "ADF") (pin "4") (pinfunction "EH_4") (pintype "unspecified+no_connect"))
    )
    (net (code "60") (name "unconnected-(ADF-EH-Pad5)") (class "Default")
      (node (ref "ADF") (pin "5") (pinfunction "EH_5") (pintype "unspecified+no_connect"))
    )
    (net (code "61") (name "unconnected-(COM1-EH-Pad4)") (class "Default")
      (node (ref "COM1") (pin "4") (pinfunction "EH_4") (pintype "unspecified+no_connect"))
    )
    (net (code "62") (name "unconnected-(COM1-EH-Pad5)") (class "Default")
      (node (ref "COM1") (pin "5") (pinfunction "EH_5") (pintype "unspecified+no_connect"))
    )
    (net (code "63") (name "unconnected-(COM1_M-Pad2)") (class "Default")
      (node (ref "COM1_M") (pin "2") (pinfunction "2_2") (pintype "unspecified+no_connect"))
    )
    (net (code "64") (name "unconnected-(COM1_M-Pad3)") (class "Default")
      (node (ref "COM1_M") (pin "3") (pinfunction "3_3") (pintype "unspecified+no_connect"))
    )
    (net (code "65") (name "unconnected-(COM2-EH-Pad4)") (class "Default")
      (node (ref "COM2") (pin "4") (pinfunction "EH_4") (pintype "unspecified+no_connect"))
    )
    (net (code "66") (name "unconnected-(COM2-EH-Pad5)") (class "Default")
      (node (ref "COM2") (pin "5") (pinfunction "EH_5") (pintype "unspecified+no_connect"))
    )
    (net (code "67") (name "unconnected-(COM2_M-Pad2)") (class "Default")
      (node (ref "COM2_M") (pin "2") (pinfunction "2_2") (pintype "unspecified+no_connect"))
    )
    (net (code "68") (name "unconnected-(COM2_M-Pad3)") (class "Default")
      (node (ref "COM2_M") (pin "3") (pinfunction "3_3") (pintype "unspecified+no_connect"))
    )
    (net (code "69") (name "unconnected-(DME1-EH-Pad4)") (class "Default")
      (node (ref "DME1") (pin "4") (pinfunction "EH_4") (pintype "unspecified+no_connect"))
    )
    (net (code "70") (name "unconnected-(DME1-EH-Pad5)") (class "Default")
      (node (ref "DME1") (pin "5") (pinfunction "EH_5") (pintype "unspecified+no_connect"))
    )
    (net (code "71") (name "unconnected-(DME2-EH-Pad4)") (class "Default")
      (node (ref "DME2") (pin "4") (pinfunction "EH_4") (pintype "unspecified+no_connect"))
    )
    (net (code "72") (name "unconnected-(DME2-EH-Pad5)") (class "Default")
      (node (ref "DME2") (pin "5") (pinfunction "EH_5") (pintype "unspecified+no_connect"))
    )
    (net (code "73") (name "unconnected-(HDPH-EH-Pad4)") (class "Default")
      (node (ref "HDPH") (pin "4") (pinfunction "EH_4") (pintype "unspecified+no_connect"))
    )
    (net (code "74") (name "unconnected-(HDPH-EH-Pad5)") (class "Default")
      (node (ref "HDPH") (pin "5") (pinfunction "EH_5") (pintype "unspecified+no_connect"))
    )
    (net (code "75") (name "unconnected-(HF-EH-Pad4)") (class "Default")
      (node (ref "HF") (pin "4") (pinfunction "EH_4") (pintype "unspecified+no_connect"))
    )
    (net (code "76") (name "unconnected-(HF-EH-Pad5)") (class "Default")
      (node (ref "HF") (pin "5") (pinfunction "EH_5") (pintype "unspecified+no_connect"))
    )
    (net (code "77") (name "unconnected-(HF_M-Pad2)") (class "Default")
      (node (ref "HF_M") (pin "2") (pinfunction "2_2") (pintype "unspecified+no_connect"))
    )
    (net (code "78") (name "unconnected-(HF_M-Pad3)") (class "Default")
      (node (ref "HF_M") (pin "3") (pinfunction "3_3") (pintype "unspecified+no_connect"))
    )
    (net (code "79") (name "unconnected-(INPH-EH-Pad4)") (class "Default")
      (node (ref "INPH") (pin "4") (pinfunction "EH_4") (pintype "unspecified+no_connect"))
    )
    (net (code "80") (name "unconnected-(INPH-EH-Pad5)") (class "Default")
      (node (ref "INPH") (pin "5") (pinfunction "EH_5") (pintype "unspecified+no_connect"))
    )
    (net (code "81") (name "unconnected-(MKR-EH-Pad4)") (class "Default")
      (node (ref "MKR") (pin "4") (pinfunction "EH_4") (pintype "unspecified+no_connect"))
    )
    (net (code "82") (name "unconnected-(MKR-EH-Pad5)") (class "Default")
      (node (ref "MKR") (pin "5") (pinfunction "EH_5") (pintype "unspecified+no_connect"))
    )
    (net (code "83") (name "unconnected-(MUTE-Pad2)") (class "Default")
      (node (ref "MUTE") (pin "2") (pinfunction "2_2") (pintype "unspecified+no_connect"))
    )
    (net (code "84") (name "unconnected-(MUTE-Pad3)") (class "Default")
      (node (ref "MUTE") (pin "3") (pinfunction "3_3") (pintype "unspecified+no_connect"))
    )
    (net (code "85") (name "unconnected-(NAV1-EH-Pad4)") (class "Default")
      (node (ref "NAV1") (pin "4") (pinfunction "EH_4") (pintype "unspecified+no_connect"))
    )
    (net (code "86") (name "unconnected-(NAV1-EH-Pad5)") (class "Default")
      (node (ref "NAV1") (pin "5") (pinfunction "EH_5") (pintype "unspecified+no_connect"))
    )
    (net (code "87") (name "unconnected-(NAV2-EH-Pad4)") (class "Default")
      (node (ref "NAV2") (pin "4") (pinfunction "EH_4") (pintype "unspecified+no_connect"))
    )
    (net (code "88") (name "unconnected-(NAV2-EH-Pad5)") (class "Default")
      (node (ref "NAV2") (pin "5") (pinfunction "EH_5") (pintype "unspecified+no_connect"))
    )
    (net (code "89") (name "unconnected-(PA-EH-Pad4)") (class "Default")
      (node (ref "PA") (pin "4") (pinfunction "EH_4") (pintype "unspecified+no_connect"))
    )
    (net (code "90") (name "unconnected-(PA-EH-Pad5)") (class "Default")
      (node (ref "PA") (pin "5") (pinfunction "EH_5") (pintype "unspecified+no_connect"))
    )
    (net (code "91") (name "unconnected-(PA_M-Pad2)") (class "Default")
      (node (ref "PA_M") (pin "2") (pinfunction "2_2") (pintype "unspecified+no_connect"))
    )
    (net (code "92") (name "unconnected-(PA_M-Pad3)") (class "Default")
      (node (ref "PA_M") (pin "3") (pinfunction "3_3") (pintype "unspecified+no_connect"))
    )
    (net (code "93") (name "unconnected-(SPKR-EH-Pad4)") (class "Default")
      (node (ref "SPKR") (pin "4") (pinfunction "EH_4") (pintype "unspecified+no_connect"))
    )
    (net (code "94") (name "unconnected-(SPKR-EH-Pad5)") (class "Default")
      (node (ref "SPKR") (pin "5") (pinfunction "EH_5") (pintype "unspecified+no_connect"))
    )
    (net (code "95") (name "unconnected-(ST-EH-Pad4)") (class "Default")
      (node (ref "ST") (pin "4") (pinfunction "EH_4") (pintype "unspecified+no_connect"))
    )
    (net (code "96") (name "unconnected-(ST-EH-Pad5)") (class "Default")
      (node (ref "ST") (pin "5") (pinfunction "EH_5") (pintype "unspecified+no_connect"))
    )
    (net (code "97") (name "unconnected-(U1-3.3V-Pad79)") (class "Default")
      (node (ref "U1") (pin "79") (pinfunction "3.3V_79") (pintype "unspecified+no_connect"))
    )
    (net (code "98") (name "unconnected-(U1-3.3V-Pad80)") (class "Default")
      (node (ref "U1") (pin "80") (pinfunction "3.3V_80") (pintype "unspecified+no_connect"))
    )
    (net (code "99") (name "unconnected-(U1-5V-Pad81)") (class "Default")
      (node (ref "U1") (pin "81") (pinfunction "5V_81") (pintype "unspecified+no_connect"))
    )
    (net (code "100") (name "unconnected-(U1-5V-Pad82)") (class "Default")
      (node (ref "U1") (pin "82") (pinfunction "5V_82") (pintype "unspecified+no_connect"))
    )
    (net (code "101") (name "unconnected-(U1-A15-Pad16)") (class "Default")
      (node (ref "U1") (pin "16") (pinfunction "A15_16") (pintype "unspecified+no_connect"))
    )
    (net (code "102") (name "unconnected-(U1-AREF-Pad78)") (class "Default")
      (node (ref "U1") (pin "78") (pinfunction "AREF_78") (pintype "unspecified+no_connect"))
    )
    (net (code "103") (name "unconnected-(U1-D6-Pad70)") (class "Default")
      (node (ref "U1") (pin "70") (pinfunction "D6_70") (pintype "unspecified+no_connect"))
    )
    (net (code "104") (name "unconnected-(U1-D7-Pad69)") (class "Default")
      (node (ref "U1") (pin "69") (pinfunction "D7_69") (pintype "unspecified+no_connect"))
    )
    (net (code "105") (name "unconnected-(U1-D8-Pad68)") (class "Default")
      (node (ref "U1") (pin "68") (pinfunction "D8_68") (pintype "unspecified+no_connect"))
    )
    (net (code "106") (name "unconnected-(U1-D9-Pad67)") (class "Default")
      (node (ref "U1") (pin "67") (pinfunction "D9_67") (pintype "unspecified+no_connect"))
    )
    (net (code "107") (name "unconnected-(U1-D10-Pad66)") (class "Default")
      (node (ref "U1") (pin "66") (pinfunction "D10_66") (pintype "unspecified+no_connect"))
    )
    (net (code "108") (name "unconnected-(U1-D11-Pad65)") (class "Default")
      (node (ref "U1") (pin "65") (pinfunction "D11_65") (pintype "unspecified+no_connect"))
    )
    (net (code "109") (name "unconnected-(U1-D14-Pad62)") (class "Default")
      (node (ref "U1") (pin "62") (pinfunction "D14_62") (pintype "unspecified+no_connect"))
    )
    (net (code "110") (name "unconnected-(U1-D15-Pad61)") (class "Default")
      (node (ref "U1") (pin "61") (pinfunction "D15_61") (pintype "unspecified+no_connect"))
    )
    (net (code "111") (name "unconnected-(U1-D16-Pad60)") (class "Default")
      (node (ref "U1") (pin "60") (pinfunction "D16_60") (pintype "unspecified+no_connect"))
    )
    (net (code "112") (name "unconnected-(U1-D17-Pad59)") (class "Default")
      (node (ref "U1") (pin "59") (pinfunction "D17_59") (pintype "unspecified+no_connect"))
    )
    (net (code "113") (name "unconnected-(U1-D18-Pad58)") (class "Default")
      (node (ref "U1") (pin "58") (pinfunction "D18_58") (pintype "unspecified+no_connect"))
    )
    (net (code "114") (name "unconnected-(U1-D19-Pad57)") (class "Default")
      (node (ref "U1") (pin "57") (pinfunction "D19_57") (pintype "unspecified+no_connect"))
    )
    (net (code "115") (name "unconnected-(U1-D20-Pad56)") (class "Default")
      (node (ref "U1") (pin "56") (pinfunction "D20_56") (pintype "unspecified+no_connect"))
    )
    (net (code "116") (name "unconnected-(U1-D21-Pad55)") (class "Default")
      (node (ref "U1") (pin "55") (pinfunction "D21_55") (pintype "unspecified+no_connect"))
    )
    (net (code "117") (name "unconnected-(U1-D22-Pad54)") (class "Default")
      (node (ref "U1") (pin "54") (pinfunction "D22_54") (pintype "unspecified+no_connect"))
    )
    (net (code "118") (name "unconnected-(U1-D23-Pad53)") (class "Default")
      (node (ref "U1") (pin "53") (pinfunction "D23_53") (pintype "unspecified+no_connect"))
    )
    (net (code "119") (name "unconnected-(U1-D24-Pad52)") (class "Default")
      (node (ref "U1") (pin "52") (pinfunction "D24_52") (pintype "unspecified+no_connect"))
    )
    (net (code "120") (name "unconnected-(U1-D25-Pad51)") (class "Default")
      (node (ref "U1") (pin "51") (pinfunction "D25_51") (pintype "unspecified+no_connect"))
    )
    (net (code "121") (name "unconnected-(U1-D26-Pad50)") (class "Default")
      (node (ref "U1") (pin "50") (pinfunction "D26_50") (pintype "unspecified+no_connect"))
    )
    (net (code "122") (name "unconnected-(U1-D27-Pad49)") (class "Default")
      (node (ref "U1") (pin "49") (pinfunction "D27_49") (pintype "unspecified+no_connect"))
    )
    (net (code "123") (name "unconnected-(U1-D28-Pad48)") (class "Default")
      (node (ref "U1") (pin "48") (pinfunction "D28_48") (pintype "unspecified+no_connect"))
    )
    (net (code "124") (name "unconnected-(U1-D29-Pad47)") (class "Default")
      (node (ref "U1") (pin "47") (pinfunction "D29_47") (pintype "unspecified+no_connect"))
    )
    (net (code "125") (name "unconnected-(U1-D30-Pad46)") (class "Default")
      (node (ref "U1") (pin "46") (pinfunction "D30_46") (pintype "unspecified+no_connect"))
    )
    (net (code "126") (name "unconnected-(U1-D31-Pad45)") (class "Default")
      (node (ref "U1") (pin "45") (pinfunction "D31_45") (pintype "unspecified+no_connect"))
    )
    (net (code "127") (name "unconnected-(U1-D40-Pad25)") (class "Default")
      (node (ref "U1") (pin "25") (pinfunction "D40_25") (pintype "unspecified+no_connect"))
    )
    (net (code "128") (name "unconnected-(U1-D41-Pad26)") (class "Default")
      (node (ref "U1") (pin "26") (pinfunction "D41_26") (pintype "unspecified+no_connect"))
    )
    (net (code "129") (name "unconnected-(U1-D42-Pad27)") (class "Default")
      (node (ref "U1") (pin "27") (pinfunction "D42_27") (pintype "unspecified+no_connect"))
    )
    (net (code "130") (name "unconnected-(U1-D43-Pad28)") (class "Default")
      (node (ref "U1") (pin "28") (pinfunction "D43_28") (pintype "unspecified+no_connect"))
    )
    (net (code "131") (name "unconnected-(U1-D44-Pad29)") (class "Default")
      (node (ref "U1") (pin "29") (pinfunction "D44_29") (pintype "unspecified+no_connect"))
    )
    (net (code "132") (name "unconnected-(U1-D45-Pad30)") (class "Default")
      (node (ref "U1") (pin "30") (pinfunction "D45_30") (pintype "unspecified+no_connect"))
    )
    (net (code "133") (name "unconnected-(U1-D46-Pad31)") (class "Default")
      (node (ref "U1") (pin "31") (pinfunction "D46_31") (pintype "unspecified+no_connect"))
    )
    (net (code "134") (name "unconnected-(U1-D47-Pad32)") (class "Default")
      (node (ref "U1") (pin "32") (pinfunction "D47_32") (pintype "unspecified+no_connect"))
    )
    (net (code "135") (name "unconnected-(U1-D48-Pad33)") (class "Default")
      (node (ref "U1") (pin "33") (pinfunction "D48_33") (pintype "unspecified+no_connect"))
    )
    (net (code "136") (name "unconnected-(U1-D49-Pad34)") (class "Default")
      (node (ref "U1") (pin "34") (pinfunction "D49_34") (pintype "unspecified+no_connect"))
    )
    (net (code "137") (name "unconnected-(U1-D50-Pad35)") (class "Default")
      (node (ref "U1") (pin "35") (pinfunction "D50_35") (pintype "unspecified+no_connect"))
    )
    (net (code "138") (name "unconnected-(U1-D51-Pad36)") (class "Default")
      (node (ref "U1") (pin "36") (pinfunction "D51_36") (pintype "unspecified+no_connect"))
    )
    (net (code "139") (name "unconnected-(U1-D52-Pad37)") (class "Default")
      (node (ref "U1") (pin "37") (pinfunction "D52_37") (pintype "unspecified+no_connect"))
    )
    (net (code "140") (name "unconnected-(U1-D53-Pad38)") (class "Default")
      (node (ref "U1") (pin "38") (pinfunction "D53_38") (pintype "unspecified+no_connect"))
    )
    (net (code "141") (name "unconnected-(U1-MISO-Pad40)") (class "Default")
      (node (ref "U1") (pin "40") (pinfunction "MISO_40") (pintype "unspecified+no_connect"))
    )
    (net (code "142") (name "unconnected-(U1-MOSI-Pad41)") (class "Default")
      (node (ref "U1") (pin "41") (pinfunction "MOSI_41") (pintype "unspecified+no_connect"))
    )
    (net (code "143") (name "unconnected-(U1-RX-Pad76)") (class "Default")
      (node (ref "U1") (pin "76") (pinfunction "RX_76") (pintype "unspecified+no_connect"))
    )
    (net (code "144") (name "unconnected-(U1-Reset-Pad44)") (class "Default")
      (node (ref "U1") (pin "44") (pinfunction "Reset_44") (pintype "unspecified+no_connect"))
    )
    (net (code "145") (name "unconnected-(U1-Reset-Pad77)") (class "Default")
      (node (ref "U1") (pin "77") (pinfunction "Reset_77") (pintype "unspecified+no_connect"))
    )
    (net (code "146") (name "unconnected-(U1-SCK-Pad42)") (class "Default")
      (node (ref "U1") (pin "42") (pinfunction "SCK_42") (pintype "unspecified+no_connect"))
    )
    (net (code "147") (name "unconnected-(U1-TX-Pad75)") (class "Default")
      (node (ref "U1") (pin "75") (pinfunction "TX_75") (pintype "unspecified+no_connect"))
    )
    (net (code "148") (name "unconnected-(U1-VIN-Pad85)") (class "Default")
      (node (ref "U1") (pin "85") (pinfunction "VIN_85") (pintype "unspecified+no_connect"))
    )
    (net (code "149") (name "unconnected-(U1-VIN-Pad86)") (class "Default")
      (node (ref "U1") (pin "86") (pinfunction "VIN_86") (pintype "unspecified+no_connect"))
    )
    (net (code "150") (name "unconnected-(V-BOTH-ID-Pad1)") (class "Default")
      (node (ref "V-BOTH-ID") (pin "1") (pinfunction "1_1") (pintype "unspecified+no_connect"))
    )
    (net (code "151") (name "unconnected-(V-BOTH-ID-Pad5)") (class "Default")
      (node (ref "V-BOTH-ID") (pin "5") (pinfunction "5_5") (pintype "unspecified+no_connect"))
    )
    (net (code "152") (name "unconnected-(V-BOTH-ID-Pad6)") (class "Default")
      (node (ref "V-BOTH-ID") (pin "6") (pinfunction "6_6") (pintype "unspecified+no_connect"))
    )
    (net (code "153") (name "unconnected-(V-BOTH-ID-Pad7)") (class "Default")
      (node (ref "V-BOTH-ID") (pin "7") (pinfunction "7_7") (pintype "unspecified+no_connect"))
    )
    (net (code "154") (name "unconnected-(V-BOTH-ID-Pad8)") (class "Default")
      (node (ref "V-BOTH-ID") (pin "8") (pinfunction "8_8") (pintype "unspecified+no_connect"))
    )
    (net (code "155") (name "unconnected-(VOX-EH-Pad4)") (class "Default")
      (node (ref "VOX") (pin "4") (pinfunction "EH_4") (pintype "unspecified+no_connect"))
    )
    (net (code "156") (name "unconnected-(VOX-EH-Pad5)") (class "Default")
      (node (ref "VOX") (pin "5") (pinfunction "EH_5") (pintype "unspecified+no_connect"))
    )
  )
)
